# Main.net
KiCad netlist of a schematic drawn in Altium Designer
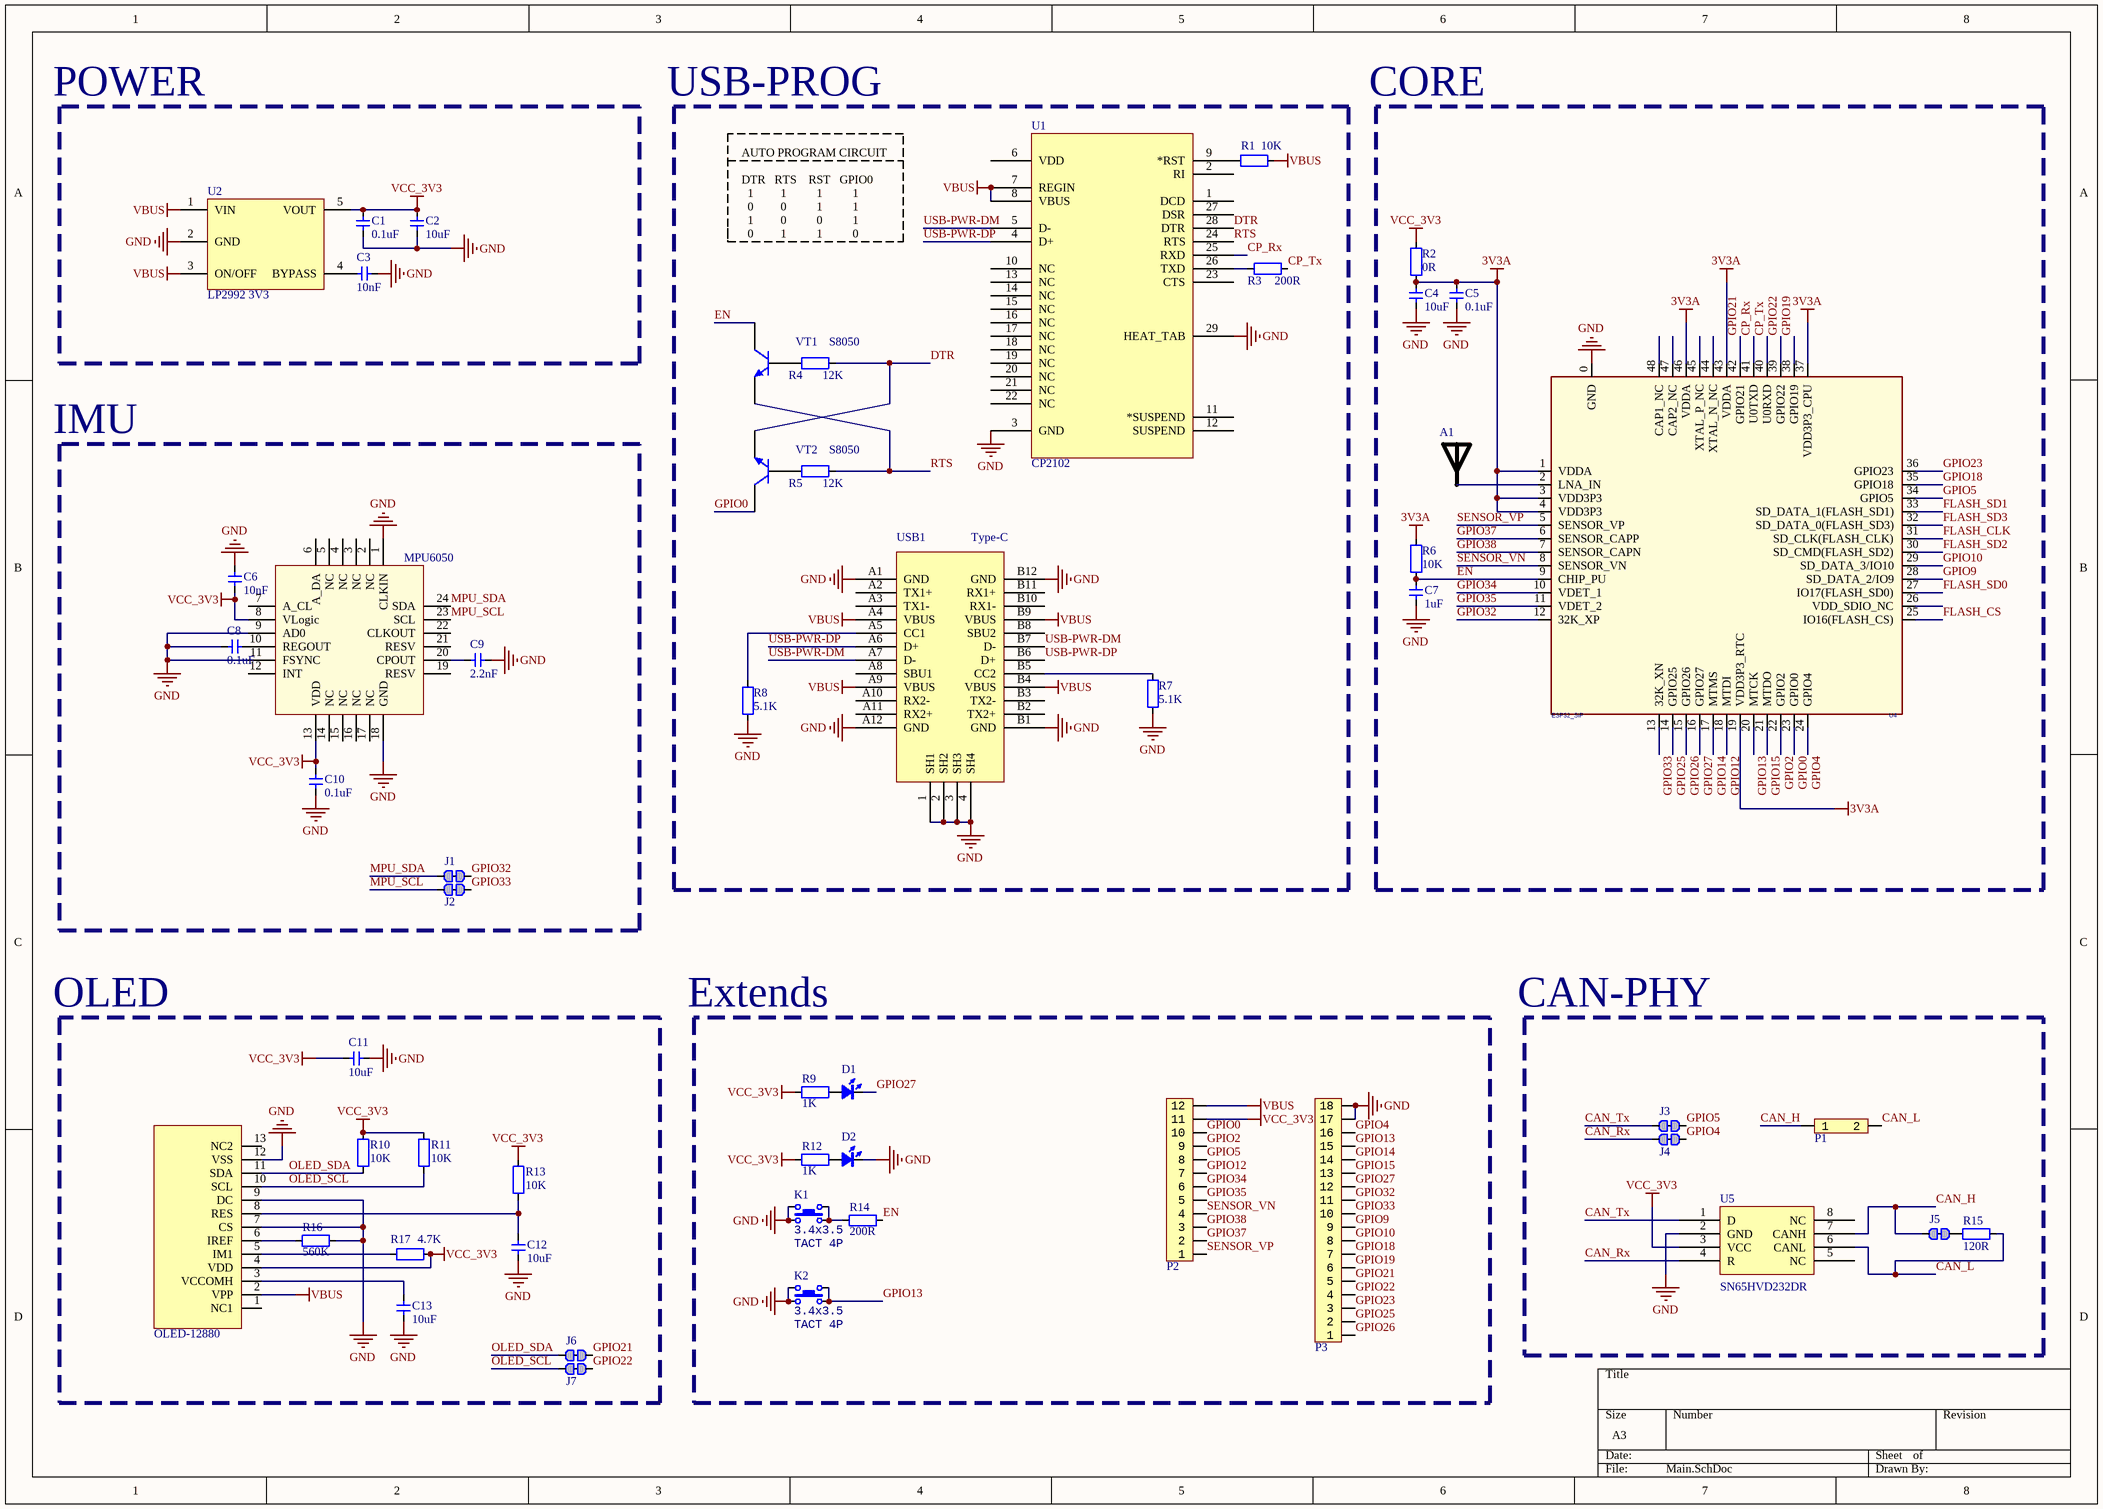
[diagram p0: Main.SchDoc]

(export (version "E")
  (design (tool "Eeschema 10.0.6"))
  (components
    (comp (ref "1")
      (value "OLED-12880")
      (footprint "OLED-12880")
      (libsource (lib "mLib") (part "OLED-12880"))
    )
    (comp (ref "A1")
      (value "RAINSUN")
      (footprint "ANT-Rainsun-AN5120")
      (libsource (lib "MyPcbLib") (part "ANT-Rainsun-AP5120"))
    )
    (comp (ref "C1")
      (value "0.1uF")
      (footprint "CAP_0402")
      (description "Capacitor")
      (libsource (lib "MyPcbLib") (part "电容-0402"))
    )
    (comp (ref "C2")
      (value "10uF")
      (footprint "CAP_0402")
      (description "Capacitor")
      (libsource (lib "MyPcbLib") (part "电容-0402"))
    )
    (comp (ref "C3")
      (value "10nF")
      (footprint "CAP_0402")
      (description "Capacitor")
      (libsource (lib "MyPcbLib") (part "电容-0402"))
    )
    (comp (ref "C4")
      (value "10uF")
      (footprint "CAP_0402")
      (description "Capacitor")
      (libsource (lib "MyPcbLib") (part "电容-0402"))
    )
    (comp (ref "C5")
      (value "0.1uF")
      (footprint "CAP_0402")
      (description "Capacitor")
      (libsource (lib "MyPcbLib") (part "电容-0402"))
    )
    (comp (ref "C6")
      (value "10nF")
      (footprint "CAP_0402")
      (description "Capacitor")
      (libsource (lib "MyPcbLib") (part "电容-0402"))
    )
    (comp (ref "C7")
      (value "1uF")
      (footprint "CAP_0402")
      (description "Capacitor")
      (libsource (lib "MyPcbLib") (part "电容-0402"))
    )
    (comp (ref "C8")
      (value "0.1uF")
      (footprint "CAP_0402")
      (description "Capacitor")
      (libsource (lib "MyPcbLib") (part "电容-0402"))
    )
    (comp (ref "C9")
      (value "2.2nF")
      (footprint "CAP_0402")
      (description "Capacitor")
      (libsource (lib "MyPcbLib") (part "电容-0402"))
    )
    (comp (ref "C10")
      (value "0.1uF")
      (footprint "CAP_0402")
      (description "Capacitor")
      (libsource (lib "MyPcbLib") (part "电容-0402"))
    )
    (comp (ref "C11")
      (value "10uF")
      (footprint "CAP_0402")
      (description "Capacitor")
      (libsource (lib "MyPcbLib") (part "电容-0402"))
    )
    (comp (ref "C12")
      (value "10uF")
      (footprint "CAP_0402")
      (description "Capacitor")
      (libsource (lib "MyPcbLib") (part "电容-0402"))
    )
    (comp (ref "C13")
      (value "10uF")
      (footprint "CAP_0402")
      (description "Capacitor")
      (libsource (lib "MyPcbLib") (part "电容-0402"))
    )
    (comp (ref "D1")
      (value "color?")
      (footprint "LED_0402_RED")
      (description "LED")
      (libsource (lib "KitSprout") (part "LED_0402"))
    )
    (comp (ref "D2")
      (value "color?")
      (footprint "LED_0402_RED")
      (description "LED")
      (libsource (lib "KitSprout") (part "LED_0402"))
    )
    (comp (ref "J1")
      (value "跳线")
      (footprint "0402-0R")
      (description "Resistor")
      (fields (field (name "PUBLISHER") "Altium Limited"))
      (libsource (lib "MyPcbLib") (part "跳线"))
    )
    (comp (ref "J2")
      (value "跳线")
      (footprint "0402-0R")
      (description "Resistor")
      (fields (field (name "PUBLISHER") "Altium Limited"))
      (libsource (lib "MyPcbLib") (part "跳线"))
    )
    (comp (ref "J3")
      (value "跳线")
      (footprint "0402-0R")
      (description "Resistor")
      (fields (field (name "PUBLISHER") "Altium Limited"))
      (libsource (lib "MyPcbLib") (part "跳线"))
    )
    (comp (ref "J4")
      (value "跳线")
      (footprint "0402-0R")
      (description "Resistor")
      (fields (field (name "PUBLISHER") "Altium Limited"))
      (libsource (lib "MyPcbLib") (part "跳线"))
    )
    (comp (ref "J5")
      (value "跳线")
      (footprint "0402-0R")
      (description "Resistor")
      (fields (field (name "PUBLISHER") "Altium Limited"))
      (libsource (lib "MyPcbLib") (part "跳线"))
    )
    (comp (ref "J6")
      (value "跳线")
      (footprint "0402-0R")
      (description "Resistor")
      (fields (field (name "PUBLISHER") "Altium Limited"))
      (libsource (lib "MyPcbLib") (part "跳线"))
    )
    (comp (ref "J7")
      (value "跳线")
      (footprint "0402-0R")
      (description "Resistor")
      (fields (field (name "PUBLISHER") "Altium Limited"))
      (libsource (lib "MyPcbLib") (part "跳线"))
    )
    (comp (ref "K1")
      (value "3.4x3.5")
      (footprint "ButtonTACT_3.5*3.55_90")
      (description "Button")
      (fields (field (name "TYPE") "TACT 4P") (field (name "Comment") "TACT 4P"))
      (libsource (lib "KitSprout") (part "ButtonTACT"))
    )
    (comp (ref "K2")
      (value "3.4x3.5")
      (footprint "ButtonTACT_3.5*3.55_90")
      (description "Button")
      (fields (field (name "TYPE") "TACT 4P") (field (name "Comment") "TACT 4P"))
      (libsource (lib "KitSprout") (part "ButtonTACT"))
    )
    (comp (ref "P1")
      (value "HDR2x1_2.54")
      (footprint "HDR1X2_2.54_180")
      (description "Header")
      (libsource (lib "KitSprout") (part "HDR2x1_2.54"))
    )
    (comp (ref "P2")
      (value "HDR1x12_2.54")
      (footprint "HDR1X12_2.54_180")
      (description "Header")
      (libsource (lib "KitSprout") (part "HDR1x12_2.54"))
    )
    (comp (ref "P3")
      (value "HDR1x18_2.54")
      (footprint "HDR1X18_2.54_180")
      (description "Header")
      (libsource (lib "KitSprout") (part "HDR1x18_2.54"))
    )
    (comp (ref "R1")
      (value "10K")
      (footprint "RES_0402")
      (description "Resistor")
      (libsource (lib "") (part "电阻-0402_1"))
    )
    (comp (ref "R2")
      (value "0R")
      (footprint "RES_0402")
      (description "Resistor")
      (libsource (lib "MyPcbLib") (part "电阻-0402"))
    )
    (comp (ref "R3")
      (value "200R")
      (footprint "RES_0402")
      (description "Resistor")
      (libsource (lib "") (part "电阻-0402_1"))
    )
    (comp (ref "R4")
      (value "12K")
      (footprint "RES_0402")
      (description "Resistor")
      (libsource (lib "") (part "电阻-0402_1"))
    )
    (comp (ref "R5")
      (value "12K")
      (footprint "RES_0402")
      (description "Resistor")
      (libsource (lib "") (part "电阻-0402_1"))
    )
    (comp (ref "R6")
      (value "10K")
      (footprint "RES_0402")
      (description "Resistor")
      (libsource (lib "MyPcbLib") (part "电阻-0402"))
    )
    (comp (ref "R7")
      (value "5.1K")
      (footprint "RES_0402")
      (description "Resistor")
      (libsource (lib "MyPcbLib") (part "电阻-0402"))
    )
    (comp (ref "R8")
      (value "5.1K")
      (footprint "RES_0402")
      (description "Resistor")
      (libsource (lib "MyPcbLib") (part "电阻-0402"))
    )
    (comp (ref "R9")
      (value "1K")
      (footprint "RES_0402")
      (description "Resistor")
      (libsource (lib "") (part "电阻-0402_2"))
    )
    (comp (ref "R10")
      (value "10K")
      (footprint "RES_0402")
      (description "Resistor")
      (libsource (lib "") (part "电阻-0402_3"))
    )
    (comp (ref "R11")
      (value "10K")
      (footprint "RES_0402")
      (description "Resistor")
      (libsource (lib "") (part "电阻-0402_3"))
    )
    (comp (ref "R12")
      (value "1K")
      (footprint "RES_0402")
      (description "Resistor")
      (libsource (lib "") (part "电阻-0402_2"))
    )
    (comp (ref "R13")
      (value "10K")
      (footprint "RES_0402")
      (description "Resistor")
      (libsource (lib "") (part "电阻-0402_3"))
    )
    (comp (ref "R14")
      (value "200R")
      (footprint "RES_0402")
      (description "Resistor")
      (libsource (lib "") (part "电阻-0402_2"))
    )
    (comp (ref "R15")
      (value "120R")
      (footprint "RES_0402")
      (description "Resistor")
      (libsource (lib "") (part "电阻-0402_2"))
    )
    (comp (ref "R16")
      (value "560K")
      (footprint "RES_0402")
      (description "Resistor")
      (libsource (lib "") (part "电阻-0402_2"))
    )
    (comp (ref "R17")
      (value "4.7K")
      (footprint "RES_0402")
      (description "Resistor")
      (libsource (lib "") (part "电阻-0402_2"))
    )
    (comp (ref "U1")
      (value "CP2102")
      (footprint "QFN-28")
      (description "USB转TTL")
      (libsource (lib "mLib") (part "CP2102"))
    )
    (comp (ref "U2")
      (value "LP2992 3V3")
      (footprint "SOT23-5")
      (description "LDO")
      (libsource (lib "MyPcbLib") (part "LP2992"))
    )
    (comp (ref "U3")
      (value "MPU6050")
      (footprint "QFN-24")
      (description "六轴传感器")
      (libsource (lib "mLib") (part "MPU6050"))
    )
    (comp (ref "U4")
      (value "ESP32_SIP")
      (footprint "QFN-48_7X7")
      (libsource (lib "MyPcbLib") (part "ESP32-PICO"))
    )
    (comp (ref "U5")
      (value "SN65HVD232D")
      (footprint "SO-8")
      (fields
        (field (name "MANUFACTURER") "Texas Instruments")
        (field (name "MANUFACTURER PART NUMBER") "SN65HVD232DR")
      )
      (libsource (lib "MyPcbLib") (part "SN65HVD232D"))
    )
    (comp (ref "USB1")
      (value "Type-C")
      (footprint "Type-C-TOP")
      (libsource (lib "MyPcbLib") (part "USB-Type-C-TOP"))
    )
    (comp (ref "VT1")
      (value "S8050")
      (footprint "SMT_TRIODE_NPN")
      (description "Surface mount NPN transistor, package SOT-23")
      (libsource (lib "MyPcbLib") (part "SMT_TRIODE_NPN"))
    )
    (comp (ref "VT2")
      (value "S8050")
      (footprint "SMT_TRIODE_NPN")
      (description "Surface mount NPN transistor, package SOT-23")
      (libsource (lib "MyPcbLib") (part "SMT_TRIODE_NPN"))
    )
  )
  (nets
    (net (code "1") (name "/CAN_H") (class "Default")
      (node (ref "J5") (pin "1") (pinfunction "1_1") (pintype "passive"))
      (node (ref "P1") (pin "1") (pinfunction "1_1") (pintype "passive"))
      (node (ref "U5") (pin "7") (pinfunction "CANH_7") (pintype "passive"))
    )
    (net (code "2") (name "/CAN_L") (class "Default")
      (node (ref "P1") (pin "2") (pinfunction "2_2") (pintype "passive"))
      (node (ref "R15") (pin "2") (pinfunction "2_2") (pintype "passive"))
      (node (ref "U5") (pin "6") (pinfunction "CANL_6") (pintype "passive"))
    )
    (net (code "3") (name "/CAN_Rx") (class "Default")
      (node (ref "J4") (pin "1") (pinfunction "1_1") (pintype "passive"))
      (node (ref "U5") (pin "4") (pinfunction "R_4") (pintype "passive"))
    )
    (net (code "4") (name "/CAN_Tx") (class "Default")
      (node (ref "J3") (pin "1") (pinfunction "1_1") (pintype "passive"))
      (node (ref "U5") (pin "1") (pinfunction "D_1") (pintype "passive"))
    )
    (net (code "5") (name "/CP_Rx") (class "Default")
      (node (ref "U1") (pin "25") (pinfunction "RXD_25") (pintype "passive"))
      (node (ref "U4") (pin "41") (pinfunction "U0TXD_41") (pintype "power_in"))
    )
    (net (code "6") (name "/CP_Tx") (class "Default")
      (node (ref "R3") (pin "1") (pinfunction "1_1") (pintype "passive"))
      (node (ref "U4") (pin "40") (pinfunction "U0RXD_40") (pintype "power_in"))
    )
    (net (code "7") (name "/DTR") (class "Default")
      (node (ref "R4") (pin "1") (pinfunction "1_1") (pintype "passive"))
      (node (ref "U1") (pin "28") (pinfunction "DTR_28") (pintype "passive"))
      (node (ref "VT2") (pin "2") (pinfunction "E_2") (pintype "passive"))
    )
    (net (code "8") (name "/EN") (class "Default")
      (node (ref "C7") (pin "1") (pinfunction "1_1") (pintype "passive"))
      (node (ref "R14") (pin "2") (pinfunction "2_2") (pintype "passive"))
      (node (ref "R6") (pin "2") (pinfunction "2_2") (pintype "passive"))
      (node (ref "U4") (pin "9") (pinfunction "CHIP_PU_9") (pintype "passive"))
      (node (ref "VT1") (pin "3") (pinfunction "C_3") (pintype "passive"))
    )
    (net (code "9") (name "/FLASH_CLK") (class "Default")
      (node (ref "U4") (pin "31") (pinfunction "SD_CLK(FLASH_CLK)_31") (pintype "passive"))
    )
    (net (code "10") (name "/FLASH_CS") (class "Default")
      (node (ref "U4") (pin "25") (pinfunction "IO16(FLASH_CS)_25") (pintype "passive"))
    )
    (net (code "11") (name "/FLASH_SD0") (class "Default")
      (node (ref "U4") (pin "27") (pinfunction "IO17(FLASH_SD0)_27") (pintype "passive"))
    )
    (net (code "12") (name "/FLASH_SD1") (class "Default")
      (node (ref "U4") (pin "33") (pinfunction "SD_DATA_1(FLASH_SD1)_33") (pintype "passive"))
    )
    (net (code "13") (name "/FLASH_SD2") (class "Default")
      (node (ref "U4") (pin "30") (pinfunction "SD_CMD(FLASH_SD2)_30") (pintype "passive"))
    )
    (net (code "14") (name "/FLASH_SD3") (class "Default")
      (node (ref "U4") (pin "32") (pinfunction "SD_DATA_0(FLASH_SD3)_32") (pintype "passive"))
    )
    (net (code "15") (name "/GPIO0") (class "Default")
      (node (ref "P2") (pin "10") (pinfunction "10_10") (pintype "passive"))
      (node (ref "U4") (pin "23") (pinfunction "GPIO0_23") (pintype "passive"))
      (node (ref "VT2") (pin "3") (pinfunction "C_3") (pintype "passive"))
    )
    (net (code "16") (name "/GPIO2") (class "Default")
      (node (ref "P2") (pin "9") (pinfunction "9_9") (pintype "passive"))
      (node (ref "U4") (pin "22") (pinfunction "GPIO2_22") (pintype "passive"))
    )
    (net (code "17") (name "/GPIO4") (class "Default")
      (node (ref "J4") (pin "2") (pinfunction "2_2") (pintype "passive"))
      (node (ref "P3") (pin "16") (pinfunction "16_16") (pintype "passive"))
      (node (ref "U4") (pin "24") (pinfunction "GPIO4_24") (pintype "passive"))
    )
    (net (code "18") (name "/GPIO5") (class "Default")
      (node (ref "J3") (pin "2") (pinfunction "2_2") (pintype "passive"))
      (node (ref "P2") (pin "8") (pinfunction "8_8") (pintype "passive"))
      (node (ref "U4") (pin "34") (pinfunction "GPIO5_34") (pintype "passive"))
    )
    (net (code "19") (name "/GPIO9") (class "Default")
      (node (ref "P3") (pin "9") (pinfunction "9_9") (pintype "passive"))
      (node (ref "U4") (pin "28") (pinfunction "SD_DATA_2/IO9_28") (pintype "passive"))
    )
    (net (code "20") (name "/GPIO10") (class "Default")
      (node (ref "P3") (pin "8") (pinfunction "8_8") (pintype "passive"))
      (node (ref "U4") (pin "29") (pinfunction "SD_DATA_3/IO10_29") (pintype "passive"))
    )
    (net (code "21") (name "/GPIO12") (class "Default")
      (node (ref "P2") (pin "7") (pinfunction "7_7") (pintype "passive"))
      (node (ref "U4") (pin "18") (pinfunction "MTDI_18") (pintype "passive"))
    )
    (net (code "22") (name "/GPIO13") (class "Default")
      (node (ref "K2") (pin "2") (pinfunction "2_2") (pintype "passive"))
      (node (ref "K2") (pin "4") (pinfunction "4_4") (pintype "passive"))
      (node (ref "P3") (pin "15") (pinfunction "15_15") (pintype "passive"))
      (node (ref "U4") (pin "20") (pinfunction "MTCK_20") (pintype "passive"))
    )
    (net (code "23") (name "/GPIO14") (class "Default")
      (node (ref "P3") (pin "14") (pinfunction "14_14") (pintype "passive"))
      (node (ref "U4") (pin "17") (pinfunction "MTMS_17") (pintype "passive"))
    )
    (net (code "24") (name "/GPIO15") (class "Default")
      (node (ref "P3") (pin "13") (pinfunction "13_13") (pintype "passive"))
      (node (ref "U4") (pin "21") (pinfunction "MTDO_21") (pintype "passive"))
    )
    (net (code "25") (name "/GPIO18") (class "Default")
      (node (ref "P3") (pin "7") (pinfunction "7_7") (pintype "passive"))
      (node (ref "U4") (pin "35") (pinfunction "GPIO18_35") (pintype "passive"))
    )
    (net (code "26") (name "/GPIO19") (class "Default")
      (node (ref "P3") (pin "6") (pinfunction "6_6") (pintype "passive"))
      (node (ref "U4") (pin "38") (pinfunction "GPIO19_38") (pintype "passive"))
    )
    (net (code "27") (name "/GPIO21") (class "Default")
      (node (ref "J6") (pin "2") (pinfunction "2_2") (pintype "passive"))
      (node (ref "P3") (pin "5") (pinfunction "5_5") (pintype "passive"))
      (node (ref "U4") (pin "42") (pinfunction "GPIO21_42") (pintype "passive"))
    )
    (net (code "28") (name "/GPIO22") (class "Default")
      (node (ref "J7") (pin "2") (pinfunction "2_2") (pintype "passive"))
      (node (ref "P3") (pin "4") (pinfunction "4_4") (pintype "passive"))
      (node (ref "U4") (pin "39") (pinfunction "GPIO22_39") (pintype "passive"))
    )
    (net (code "29") (name "/GPIO23") (class "Default")
      (node (ref "P3") (pin "3") (pinfunction "3_3") (pintype "passive"))
      (node (ref "U4") (pin "36") (pinfunction "GPIO23_36") (pintype "passive"))
    )
    (net (code "30") (name "/GPIO25") (class "Default")
      (node (ref "P3") (pin "2") (pinfunction "2_2") (pintype "passive"))
      (node (ref "U4") (pin "14") (pinfunction "GPIO25_14") (pintype "passive"))
    )
    (net (code "31") (name "/GPIO26") (class "Default")
      (node (ref "P3") (pin "1") (pinfunction "1_1") (pintype "passive"))
      (node (ref "U4") (pin "15") (pinfunction "GPIO26_15") (pintype "passive"))
    )
    (net (code "32") (name "/GPIO27") (class "Default")
      (node (ref "D1") (pin "2") (pinfunction "K_2") (pintype "passive"))
      (node (ref "P3") (pin "12") (pinfunction "12_12") (pintype "passive"))
      (node (ref "U4") (pin "16") (pinfunction "GPIO27_16") (pintype "passive"))
    )
    (net (code "33") (name "/GPIO32") (class "Default")
      (node (ref "J1") (pin "2") (pinfunction "2_2") (pintype "passive"))
      (node (ref "P3") (pin "11") (pinfunction "11_11") (pintype "passive"))
      (node (ref "U4") (pin "12") (pinfunction "32K_XP_12") (pintype "passive"))
    )
    (net (code "34") (name "/GPIO33") (class "Default")
      (node (ref "J2") (pin "2") (pinfunction "2_2") (pintype "passive"))
      (node (ref "P3") (pin "10") (pinfunction "10_10") (pintype "passive"))
      (node (ref "U4") (pin "13") (pinfunction "32K_XN_13") (pintype "passive"))
    )
    (net (code "35") (name "/GPIO34") (class "Default")
      (node (ref "P2") (pin "6") (pinfunction "6_6") (pintype "passive"))
      (node (ref "U4") (pin "10") (pinfunction "VDET_1_10") (pintype "passive"))
    )
    (net (code "36") (name "/GPIO35") (class "Default")
      (node (ref "P2") (pin "5") (pinfunction "5_5") (pintype "passive"))
      (node (ref "U4") (pin "11") (pinfunction "VDET_2_11") (pintype "passive"))
    )
    (net (code "37") (name "/GPIO37") (class "Default")
      (node (ref "P2") (pin "2") (pinfunction "2_2") (pintype "passive"))
      (node (ref "U4") (pin "6") (pinfunction "SENSOR_CAPP_6") (pintype "passive"))
    )
    (net (code "38") (name "/GPIO38") (class "Default")
      (node (ref "P2") (pin "3") (pinfunction "3_3") (pintype "passive"))
      (node (ref "U4") (pin "7") (pinfunction "SENSOR_CAPN_7") (pintype "passive"))
    )
    (net (code "39") (name "/MPU_SCL") (class "Default")
      (node (ref "J2") (pin "1") (pinfunction "1_1") (pintype "passive"))
      (node (ref "U3") (pin "23") (pinfunction "SCL_23") (pintype "passive"))
    )
    (net (code "40") (name "/MPU_SDA") (class "Default")
      (node (ref "J1") (pin "1") (pinfunction "1_1") (pintype "passive"))
      (node (ref "U3") (pin "24") (pinfunction "SDA_24") (pintype "passive"))
    )
    (net (code "41") (name "/OLED_SCL") (class "Default")
      (node (ref "1") (pin "10") (pinfunction "SCL_10") (pintype "passive"))
      (node (ref "J7") (pin "1") (pinfunction "1_1") (pintype "passive"))
      (node (ref "R11") (pin "1") (pinfunction "1_1") (pintype "passive"))
    )
    (net (code "42") (name "/OLED_SDA") (class "Default")
      (node (ref "1") (pin "11") (pinfunction "SDA_11") (pintype "passive"))
      (node (ref "J6") (pin "1") (pinfunction "1_1") (pintype "passive"))
      (node (ref "R10") (pin "1") (pinfunction "1_1") (pintype "passive"))
    )
    (net (code "43") (name "/RTS") (class "Default")
      (node (ref "R5") (pin "1") (pinfunction "1_1") (pintype "passive"))
      (node (ref "U1") (pin "24") (pinfunction "RTS_24") (pintype "passive"))
      (node (ref "VT1") (pin "2") (pinfunction "E_2") (pintype "passive"))
    )
    (net (code "44") (name "/SENSOR_VN") (class "Default")
      (node (ref "P2") (pin "4") (pinfunction "4_4") (pintype "passive"))
      (node (ref "U4") (pin "8") (pinfunction "SENSOR_VN_8") (pintype "passive"))
    )
    (net (code "45") (name "/SENSOR_VP") (class "Default")
      (node (ref "P2") (pin "1") (pinfunction "1_1") (pintype "passive"))
      (node (ref "U4") (pin "5") (pinfunction "SENSOR_VP_5") (pintype "passive"))
    )
    (net (code "46") (name "/USB-PWR-DM") (class "Default")
      (node (ref "U1") (pin "5") (pinfunction "D-_5") (pintype "passive"))
      (node (ref "USB1") (pin "A7") (pinfunction "D-_A7") (pintype "passive"))
      (node (ref "USB1") (pin "B7") (pinfunction "D-_B7") (pintype "passive"))
    )
    (net (code "47") (name "/USB-PWR-DP") (class "Default")
      (node (ref "U1") (pin "4") (pinfunction "D+_4") (pintype "passive"))
      (node (ref "USB1") (pin "A6") (pinfunction "D+_A6") (pintype "passive"))
      (node (ref "USB1") (pin "B6") (pinfunction "D+_B6") (pintype "passive"))
    )
    (net (code "48") (name "3V3A") (class "Default")
      (node (ref "C4") (pin "2") (pinfunction "2_2") (pintype "passive"))
      (node (ref "C5") (pin "2") (pinfunction "2_2") (pintype "passive"))
      (node (ref "R2") (pin "2") (pinfunction "2_2") (pintype "passive"))
      (node (ref "R6") (pin "1") (pinfunction "1_1") (pintype "passive"))
      (node (ref "U4") (pin "1") (pinfunction "VDDA_1") (pintype "power_in"))
      (node (ref "U4") (pin "19") (pinfunction "VDD3P3_RTC_19") (pintype "power_in"))
      (node (ref "U4") (pin "3") (pinfunction "VDD3P3_3") (pintype "power_in"))
      (node (ref "U4") (pin "37") (pinfunction "VDD3P3_CPU_37") (pintype "power_in"))
      (node (ref "U4") (pin "4") (pinfunction "VDD3P3_4") (pintype "power_in"))
      (node (ref "U4") (pin "43") (pinfunction "VDDA_43") (pintype "power_in"))
      (node (ref "U4") (pin "46") (pinfunction "VDDA_46") (pintype "power_in"))
    )
    (net (code "49") (name "GND") (class "Default")
      (node (ref "1") (pin "12") (pinfunction "VSS_12") (pintype "passive"))
      (node (ref "1") (pin "7") (pinfunction "CS_7") (pintype "passive"))
      (node (ref "1") (pin "9") (pinfunction "DC_9") (pintype "passive"))
      (node (ref "C1") (pin "1") (pinfunction "1_1") (pintype "passive"))
      (node (ref "C10") (pin "1") (pinfunction "1_1") (pintype "passive"))
      (node (ref "C11") (pin "1") (pinfunction "1_1") (pintype "passive"))
      (node (ref "C12") (pin "1") (pinfunction "1_1") (pintype "passive"))
      (node (ref "C13") (pin "1") (pinfunction "1_1") (pintype "passive"))
      (node (ref "C2") (pin "1") (pinfunction "1_1") (pintype "passive"))
      (node (ref "C3") (pin "1") (pinfunction "1_1") (pintype "passive"))
      (node (ref "C4") (pin "1") (pinfunction "1_1") (pintype "passive"))
      (node (ref "C5") (pin "1") (pinfunction "1_1") (pintype "passive"))
      (node (ref "C6") (pin "2") (pinfunction "2_2") (pintype "passive"))
      (node (ref "C7") (pin "2") (pinfunction "2_2") (pintype "passive"))
      (node (ref "C8") (pin "2") (pinfunction "2_2") (pintype "passive"))
      (node (ref "C9") (pin "1") (pinfunction "1_1") (pintype "passive"))
      (node (ref "D2") (pin "2") (pinfunction "K_2") (pintype "passive"))
      (node (ref "K1") (pin "1") (pinfunction "1_1") (pintype "passive"))
      (node (ref "K1") (pin "3") (pinfunction "3_3") (pintype "passive"))
      (node (ref "K2") (pin "1") (pinfunction "1_1") (pintype "passive"))
      (node (ref "K2") (pin "3") (pinfunction "3_3") (pintype "passive"))
      (node (ref "P3") (pin "17") (pinfunction "17_17") (pintype "passive"))
      (node (ref "P3") (pin "18") (pinfunction "18_18") (pintype "passive"))
      (node (ref "R16") (pin "2") (pinfunction "2_2") (pintype "passive"))
      (node (ref "R7") (pin "2") (pinfunction "2_2") (pintype "passive"))
      (node (ref "R8") (pin "2") (pinfunction "2_2") (pintype "passive"))
      (node (ref "U1") (pin "29") (pinfunction "HEAT_TAB_29") (pintype "passive"))
      (node (ref "U1") (pin "3") (pinfunction "GND_3") (pintype "passive"))
      (node (ref "U2") (pin "2") (pinfunction "GND_2") (pintype "passive"))
      (node (ref "U3") (pin "1") (pinfunction "CLKIN_1") (pintype "passive"))
      (node (ref "U3") (pin "11") (pinfunction "FSYNC_11") (pintype "passive"))
      (node (ref "U3") (pin "18") (pinfunction "GND_18") (pintype "passive"))
      (node (ref "U3") (pin "9") (pinfunction "AD0_9") (pintype "passive"))
      (node (ref "U4") (pin "0") (pinfunction "GND_0") (pintype "power_in"))
      (node (ref "U5") (pin "2") (pinfunction "GND_2") (pintype "passive"))
      (node (ref "USB1") (pin "1") (pinfunction "SH1_1") (pintype "passive"))
      (node (ref "USB1") (pin "2") (pinfunction "SH2_2") (pintype "passive"))
      (node (ref "USB1") (pin "3") (pinfunction "SH3_3") (pintype "passive"))
      (node (ref "USB1") (pin "4") (pinfunction "SH4_4") (pintype "passive"))
      (node (ref "USB1") (pin "A1") (pinfunction "GND_A1") (pintype "passive"))
      (node (ref "USB1") (pin "A12") (pinfunction "GND_A12") (pintype "passive"))
      (node (ref "USB1") (pin "B1") (pinfunction "GND_B1") (pintype "passive"))
      (node (ref "USB1") (pin "B12") (pinfunction "GND_B12") (pintype "passive"))
    )
    (net (code "50") (name "Net-(1-IM1)") (class "Default")
      (node (ref "1") (pin "5") (pinfunction "IM1_5") (pintype "passive"))
      (node (ref "R17") (pin "1") (pinfunction "1_1") (pintype "passive"))
    )
    (net (code "51") (name "Net-(1-IREF)") (class "Default")
      (node (ref "1") (pin "6") (pinfunction "IREF_6") (pintype "passive"))
      (node (ref "R16") (pin "1") (pinfunction "1_1") (pintype "passive"))
    )
    (net (code "52") (name "Net-(1-RES)") (class "Default")
      (node (ref "1") (pin "8") (pinfunction "RES_8") (pintype "passive"))
      (node (ref "C12") (pin "2") (pinfunction "2_2") (pintype "passive"))
      (node (ref "R13") (pin "1") (pinfunction "1_1") (pintype "passive"))
    )
    (net (code "53") (name "Net-(1-VCCOMH)") (class "Default")
      (node (ref "1") (pin "3") (pinfunction "VCCOMH_3") (pintype "passive"))
      (node (ref "C13") (pin "2") (pinfunction "2_2") (pintype "passive"))
    )
    (net (code "54") (name "Net-(D1-A)") (class "Default")
      (node (ref "D1") (pin "1") (pinfunction "A_1") (pintype "passive"))
      (node (ref "R9") (pin "2") (pinfunction "2_2") (pintype "passive"))
    )
    (net (code "55") (name "Net-(D2-A)") (class "Default")
      (node (ref "D2") (pin "1") (pinfunction "A_1") (pintype "passive"))
      (node (ref "R12") (pin "2") (pinfunction "2_2") (pintype "passive"))
    )
    (net (code "56") (name "Net-(J5-Pad2)") (class "Default")
      (node (ref "J5") (pin "2") (pinfunction "2_2") (pintype "passive"))
      (node (ref "R15") (pin "1") (pinfunction "1_1") (pintype "passive"))
    )
    (net (code "57") (name "Net-(K1-Pad2)") (class "Default")
      (node (ref "K1") (pin "2") (pinfunction "2_2") (pintype "passive"))
      (node (ref "K1") (pin "4") (pinfunction "4_4") (pintype "passive"))
      (node (ref "R14") (pin "1") (pinfunction "1_1") (pintype "passive"))
    )
    (net (code "58") (name "Net-(U1-*RST)") (class "Default")
      (node (ref "R1") (pin "2") (pinfunction "2_2") (pintype "passive"))
      (node (ref "U1") (pin "9") (pinfunction "*RST_9") (pintype "passive"))
    )
    (net (code "59") (name "Net-(U1-TXD)") (class "Default")
      (node (ref "R3") (pin "2") (pinfunction "2_2") (pintype "passive"))
      (node (ref "U1") (pin "26") (pinfunction "TXD_26") (pintype "passive"))
    )
    (net (code "60") (name "Net-(U2-BYPASS)") (class "Default")
      (node (ref "C3") (pin "2") (pinfunction "2_2") (pintype "passive"))
      (node (ref "U2") (pin "4") (pinfunction "BYPASS_4") (pintype "passive"))
    )
    (net (code "61") (name "Net-(U3-CPOUT)") (class "Default")
      (node (ref "C9") (pin "2") (pinfunction "2_2") (pintype "passive"))
      (node (ref "U3") (pin "20") (pinfunction "CPOUT_20") (pintype "passive"))
    )
    (net (code "62") (name "Net-(U3-REGOUT)") (class "Default")
      (node (ref "C8") (pin "1") (pinfunction "1_1") (pintype "passive"))
      (node (ref "U3") (pin "10") (pinfunction "REGOUT_10") (pintype "passive"))
    )
    (net (code "63") (name "Net-(U4-LNA_IN)") (class "Default")
      (node (ref "A1") (pin "1") (pinfunction "1_1") (pintype "passive"))
      (node (ref "U4") (pin "2") (pinfunction "LNA_IN_2") (pintype "passive"))
    )
    (net (code "64") (name "Net-(USB1-CC1)") (class "Default")
      (node (ref "R8") (pin "1") (pinfunction "1_1") (pintype "passive"))
      (node (ref "USB1") (pin "A5") (pinfunction "CC1_A5") (pintype "passive"))
    )
    (net (code "65") (name "Net-(USB1-CC2)") (class "Default")
      (node (ref "R7") (pin "1") (pinfunction "1_1") (pintype "passive"))
      (node (ref "USB1") (pin "B5") (pinfunction "CC2_B5") (pintype "passive"))
    )
    (net (code "66") (name "Net-(VT1-B)") (class "Default")
      (node (ref "R4") (pin "2") (pinfunction "2_2") (pintype "passive"))
      (node (ref "VT1") (pin "1") (pinfunction "B_1") (pintype "passive"))
    )
    (net (code "67") (name "Net-(VT2-B)") (class "Default")
      (node (ref "R5") (pin "2") (pinfunction "2_2") (pintype "passive"))
      (node (ref "VT2") (pin "1") (pinfunction "B_1") (pintype "passive"))
    )
    (net (code "68") (name "VBUS") (class "Default")
      (node (ref "1") (pin "2") (pinfunction "VPP_2") (pintype "passive"))
      (node (ref "P2") (pin "12") (pinfunction "12_12") (pintype "passive"))
      (node (ref "R1") (pin "1") (pinfunction "1_1") (pintype "passive"))
      (node (ref "U1") (pin "7") (pinfunction "REGIN_7") (pintype "passive"))
      (node (ref "U1") (pin "8") (pinfunction "VBUS_8") (pintype "passive"))
      (node (ref "U2") (pin "1") (pinfunction "VIN_1") (pintype "passive"))
      (node (ref "U2") (pin "3") (pinfunction "ON/OFF_3") (pintype "passive"))
      (node (ref "USB1") (pin "A4") (pinfunction "VBUS_A4") (pintype "passive"))
      (node (ref "USB1") (pin "A9") (pinfunction "VBUS_A9") (pintype "passive"))
      (node (ref "USB1") (pin "B4") (pinfunction "VBUS_B4") (pintype "passive"))
      (node (ref "USB1") (pin "B9") (pinfunction "VBUS_B9") (pintype "passive"))
    )
    (net (code "69") (name "VCC_3V3") (class "Default")
      (node (ref "1") (pin "4") (pinfunction "VDD_4") (pintype "passive"))
      (node (ref "C1") (pin "2") (pinfunction "2_2") (pintype "passive"))
      (node (ref "C10") (pin "2") (pinfunction "2_2") (pintype "passive"))
      (node (ref "C11") (pin "2") (pinfunction "2_2") (pintype "passive"))
      (node (ref "C2") (pin "2") (pinfunction "2_2") (pintype "passive"))
      (node (ref "C6") (pin "1") (pinfunction "1_1") (pintype "passive"))
      (node (ref "P2") (pin "11") (pinfunction "11_11") (pintype "passive"))
      (node (ref "R10") (pin "2") (pinfunction "2_2") (pintype "passive"))
      (node (ref "R11") (pin "2") (pinfunction "2_2") (pintype "passive"))
      (node (ref "R12") (pin "1") (pinfunction "1_1") (pintype "passive"))
      (node (ref "R13") (pin "2") (pinfunction "2_2") (pintype "passive"))
      (node (ref "R17") (pin "2") (pinfunction "2_2") (pintype "passive"))
      (node (ref "R2") (pin "1") (pinfunction "1_1") (pintype "passive"))
      (node (ref "R9") (pin "1") (pinfunction "1_1") (pintype "passive"))
      (node (ref "U2") (pin "5") (pinfunction "VOUT_5") (pintype "passive"))
      (node (ref "U3") (pin "13") (pinfunction "VDD_13") (pintype "passive"))
      (node (ref "U3") (pin "8") (pinfunction "VLogic_8") (pintype "passive"))
      (node (ref "U5") (pin "3") (pinfunction "VCC_3") (pintype "passive"))
    )
    (net (code "70") (name "unconnected-(1-NC1-Pad1)") (class "Default")
      (node (ref "1") (pin "1") (pinfunction "NC1_1") (pintype "passive"))
    )
    (net (code "71") (name "unconnected-(1-NC2-Pad13)") (class "Default")
      (node (ref "1") (pin "13") (pinfunction "NC2_13") (pintype "passive"))
    )
    (net (code "72") (name "unconnected-(U1-*SUSPEND-Pad11)") (class "Default")
      (node (ref "U1") (pin "11") (pinfunction "*SUSPEND_11") (pintype "passive"))
    )
    (net (code "73") (name "unconnected-(U1-CTS-Pad23)") (class "Default")
      (node (ref "U1") (pin "23") (pinfunction "CTS_23") (pintype "passive"))
    )
    (net (code "74") (name "unconnected-(U1-DCD-Pad1)") (class "Default")
      (node (ref "U1") (pin "1") (pinfunction "DCD_1") (pintype "passive"))
    )
    (net (code "75") (name "unconnected-(U1-DSR-Pad27)") (class "Default")
      (node (ref "U1") (pin "27") (pinfunction "DSR_27") (pintype "passive"))
    )
    (net (code "76") (name "unconnected-(U1-NC-Pad10)") (class "Default")
      (node (ref "U1") (pin "10") (pinfunction "NC_10") (pintype "passive"))
    )
    (net (code "77") (name "unconnected-(U1-NC-Pad13)") (class "Default")
      (node (ref "U1") (pin "13") (pinfunction "NC_13") (pintype "passive"))
    )
    (net (code "78") (name "unconnected-(U1-NC-Pad14)") (class "Default")
      (node (ref "U1") (pin "14") (pinfunction "NC_14") (pintype "passive"))
    )
    (net (code "79") (name "unconnected-(U1-NC-Pad15)") (class "Default")
      (node (ref "U1") (pin "15") (pinfunction "NC_15") (pintype "passive"))
    )
    (net (code "80") (name "unconnected-(U1-NC-Pad16)") (class "Default")
      (node (ref "U1") (pin "16") (pinfunction "NC_16") (pintype "passive"))
    )
    (net (code "81") (name "unconnected-(U1-NC-Pad17)") (class "Default")
      (node (ref "U1") (pin "17") (pinfunction "NC_17") (pintype "passive"))
    )
    (net (code "82") (name "unconnected-(U1-NC-Pad18)") (class "Default")
      (node (ref "U1") (pin "18") (pinfunction "NC_18") (pintype "passive"))
    )
    (net (code "83") (name "unconnected-(U1-NC-Pad19)") (class "Default")
      (node (ref "U1") (pin "19") (pinfunction "NC_19") (pintype "passive"))
    )
    (net (code "84") (name "unconnected-(U1-NC-Pad20)") (class "Default")
      (node (ref "U1") (pin "20") (pinfunction "NC_20") (pintype "passive"))
    )
    (net (code "85") (name "unconnected-(U1-NC-Pad21)") (class "Default")
      (node (ref "U1") (pin "21") (pinfunction "NC_21") (pintype "passive"))
    )
    (net (code "86") (name "unconnected-(U1-NC-Pad22)") (class "Default")
      (node (ref "U1") (pin "22") (pinfunction "NC_22") (pintype "passive"))
    )
    (net (code "87") (name "unconnected-(U1-RI-Pad2)") (class "Default")
      (node (ref "U1") (pin "2") (pinfunction "RI_2") (pintype "passive"))
    )
    (net (code "88") (name "unconnected-(U1-SUSPEND-Pad12)") (class "Default")
      (node (ref "U1") (pin "12") (pinfunction "SUSPEND_12") (pintype "passive"))
    )
    (net (code "89") (name "unconnected-(U1-VDD-Pad6)") (class "Default")
      (node (ref "U1") (pin "6") (pinfunction "VDD_6") (pintype "passive"))
    )
    (net (code "90") (name "unconnected-(U3-A_CL-Pad7)") (class "Default")
      (node (ref "U3") (pin "7") (pinfunction "A_CL_7") (pintype "passive"))
    )
    (net (code "91") (name "unconnected-(U3-A_DA-Pad6)") (class "Default")
      (node (ref "U3") (pin "6") (pinfunction "A_DA_6") (pintype "passive"))
    )
    (net (code "92") (name "unconnected-(U3-CLKOUT-Pad22)") (class "Default")
      (node (ref "U3") (pin "22") (pinfunction "CLKOUT_22") (pintype "passive"))
    )
    (net (code "93") (name "unconnected-(U3-INT-Pad12)") (class "Default")
      (node (ref "U3") (pin "12") (pinfunction "INT_12") (pintype "passive"))
    )
    (net (code "94") (name "unconnected-(U3-NC-Pad2)") (class "Default")
      (node (ref "U3") (pin "2") (pinfunction "NC_2") (pintype "passive"))
    )
    (net (code "95") (name "unconnected-(U3-NC-Pad3)") (class "Default")
      (node (ref "U3") (pin "3") (pinfunction "NC_3") (pintype "passive"))
    )
    (net (code "96") (name "unconnected-(U3-NC-Pad4)") (class "Default")
      (node (ref "U3") (pin "4") (pinfunction "NC_4") (pintype "passive"))
    )
    (net (code "97") (name "unconnected-(U3-NC-Pad5)") (class "Default")
      (node (ref "U3") (pin "5") (pinfunction "NC_5") (pintype "passive"))
    )
    (net (code "98") (name "unconnected-(U3-NC-Pad14)") (class "Default")
      (node (ref "U3") (pin "14") (pinfunction "NC_14") (pintype "passive"))
    )
    (net (code "99") (name "unconnected-(U3-NC-Pad15)") (class "Default")
      (node (ref "U3") (pin "15") (pinfunction "NC_15") (pintype "passive"))
    )
    (net (code "100") (name "unconnected-(U3-NC-Pad16)") (class "Default")
      (node (ref "U3") (pin "16") (pinfunction "NC_16") (pintype "passive"))
    )
    (net (code "101") (name "unconnected-(U3-NC-Pad17)") (class "Default")
      (node (ref "U3") (pin "17") (pinfunction "NC_17") (pintype "passive"))
    )
    (net (code "102") (name "unconnected-(U3-RESV-Pad19)") (class "Default")
      (node (ref "U3") (pin "19") (pinfunction "RESV_19") (pintype "passive"))
    )
    (net (code "103") (name "unconnected-(U3-RESV-Pad21)") (class "Default")
      (node (ref "U3") (pin "21") (pinfunction "RESV_21") (pintype "passive"))
    )
    (net (code "104") (name "unconnected-(U4-CAP1_NC-Pad48)") (class "Default")
      (node (ref "U4") (pin "48") (pinfunction "CAP1_NC_48") (pintype "passive"))
    )
    (net (code "105") (name "unconnected-(U4-CAP2_NC-Pad47)") (class "Default")
      (node (ref "U4") (pin "47") (pinfunction "CAP2_NC_47") (pintype "passive"))
    )
    (net (code "106") (name "unconnected-(U4-VDD_SDIO_NC-Pad26)") (class "Default")
      (node (ref "U4") (pin "26") (pinfunction "VDD_SDIO_NC_26") (pintype "passive"))
    )
    (net (code "107") (name "unconnected-(U4-XTAL_N_NC-Pad44)") (class "Default")
      (node (ref "U4") (pin "44") (pinfunction "XTAL_N_NC_44") (pintype "passive"))
    )
    (net (code "108") (name "unconnected-(U4-XTAL_P_NC-Pad45)") (class "Default")
      (node (ref "U4") (pin "45") (pinfunction "XTAL_P_NC_45") (pintype "passive"))
    )
    (net (code "109") (name "unconnected-(U5-NC-Pad5)") (class "Default")
      (node (ref "U5") (pin "5") (pinfunction "NC_5") (pintype "passive"))
    )
    (net (code "110") (name "unconnected-(U5-NC-Pad8)") (class "Default")
      (node (ref "U5") (pin "8") (pinfunction "NC_8") (pintype "passive"))
    )
    (net (code "111") (name "unconnected-(USB1-RX1+-PadB11)") (class "Default")
      (node (ref "USB1") (pin "B11") (pinfunction "RX1+_B11") (pintype "passive"))
    )
    (net (code "112") (name "unconnected-(USB1-RX1--PadB10)") (class "Default")
      (node (ref "USB1") (pin "B10") (pinfunction "RX1-_B10") (pintype "passive"))
    )
    (net (code "113") (name "unconnected-(USB1-RX2+-PadA11)") (class "Default")
      (node (ref "USB1") (pin "A11") (pinfunction "RX2+_A11") (pintype "passive"))
    )
    (net (code "114") (name "unconnected-(USB1-RX2--PadA10)") (class "Default")
      (node (ref "USB1") (pin "A10") (pinfunction "RX2-_A10") (pintype "passive"))
    )
    (net (code "115") (name "unconnected-(USB1-SBU1-PadA8)") (class "Default")
      (node (ref "USB1") (pin "A8") (pinfunction "SBU1_A8") (pintype "passive"))
    )
    (net (code "116") (name "unconnected-(USB1-SBU2-PadB8)") (class "Default")
      (node (ref "USB1") (pin "B8") (pinfunction "SBU2_B8") (pintype "passive"))
    )
    (net (code "117") (name "unconnected-(USB1-TX1+-PadA2)") (class "Default")
      (node (ref "USB1") (pin "A2") (pinfunction "TX1+_A2") (pintype "passive"))
    )
    (net (code "118") (name "unconnected-(USB1-TX1--PadA3)") (class "Default")
      (node (ref "USB1") (pin "A3") (pinfunction "TX1-_A3") (pintype "passive"))
    )
    (net (code "119") (name "unconnected-(USB1-TX2+-PadB2)") (class "Default")
      (node (ref "USB1") (pin "B2") (pinfunction "TX2+_B2") (pintype "passive"))
    )
    (net (code "120") (name "unconnected-(USB1-TX2--PadB3)") (class "Default")
      (node (ref "USB1") (pin "B3") (pinfunction "TX2-_B3") (pintype "passive"))
    )
  )
)
